# SHIELD_PICO_SMD.net
KiCad netlist of a schematic drawn in EAGLE
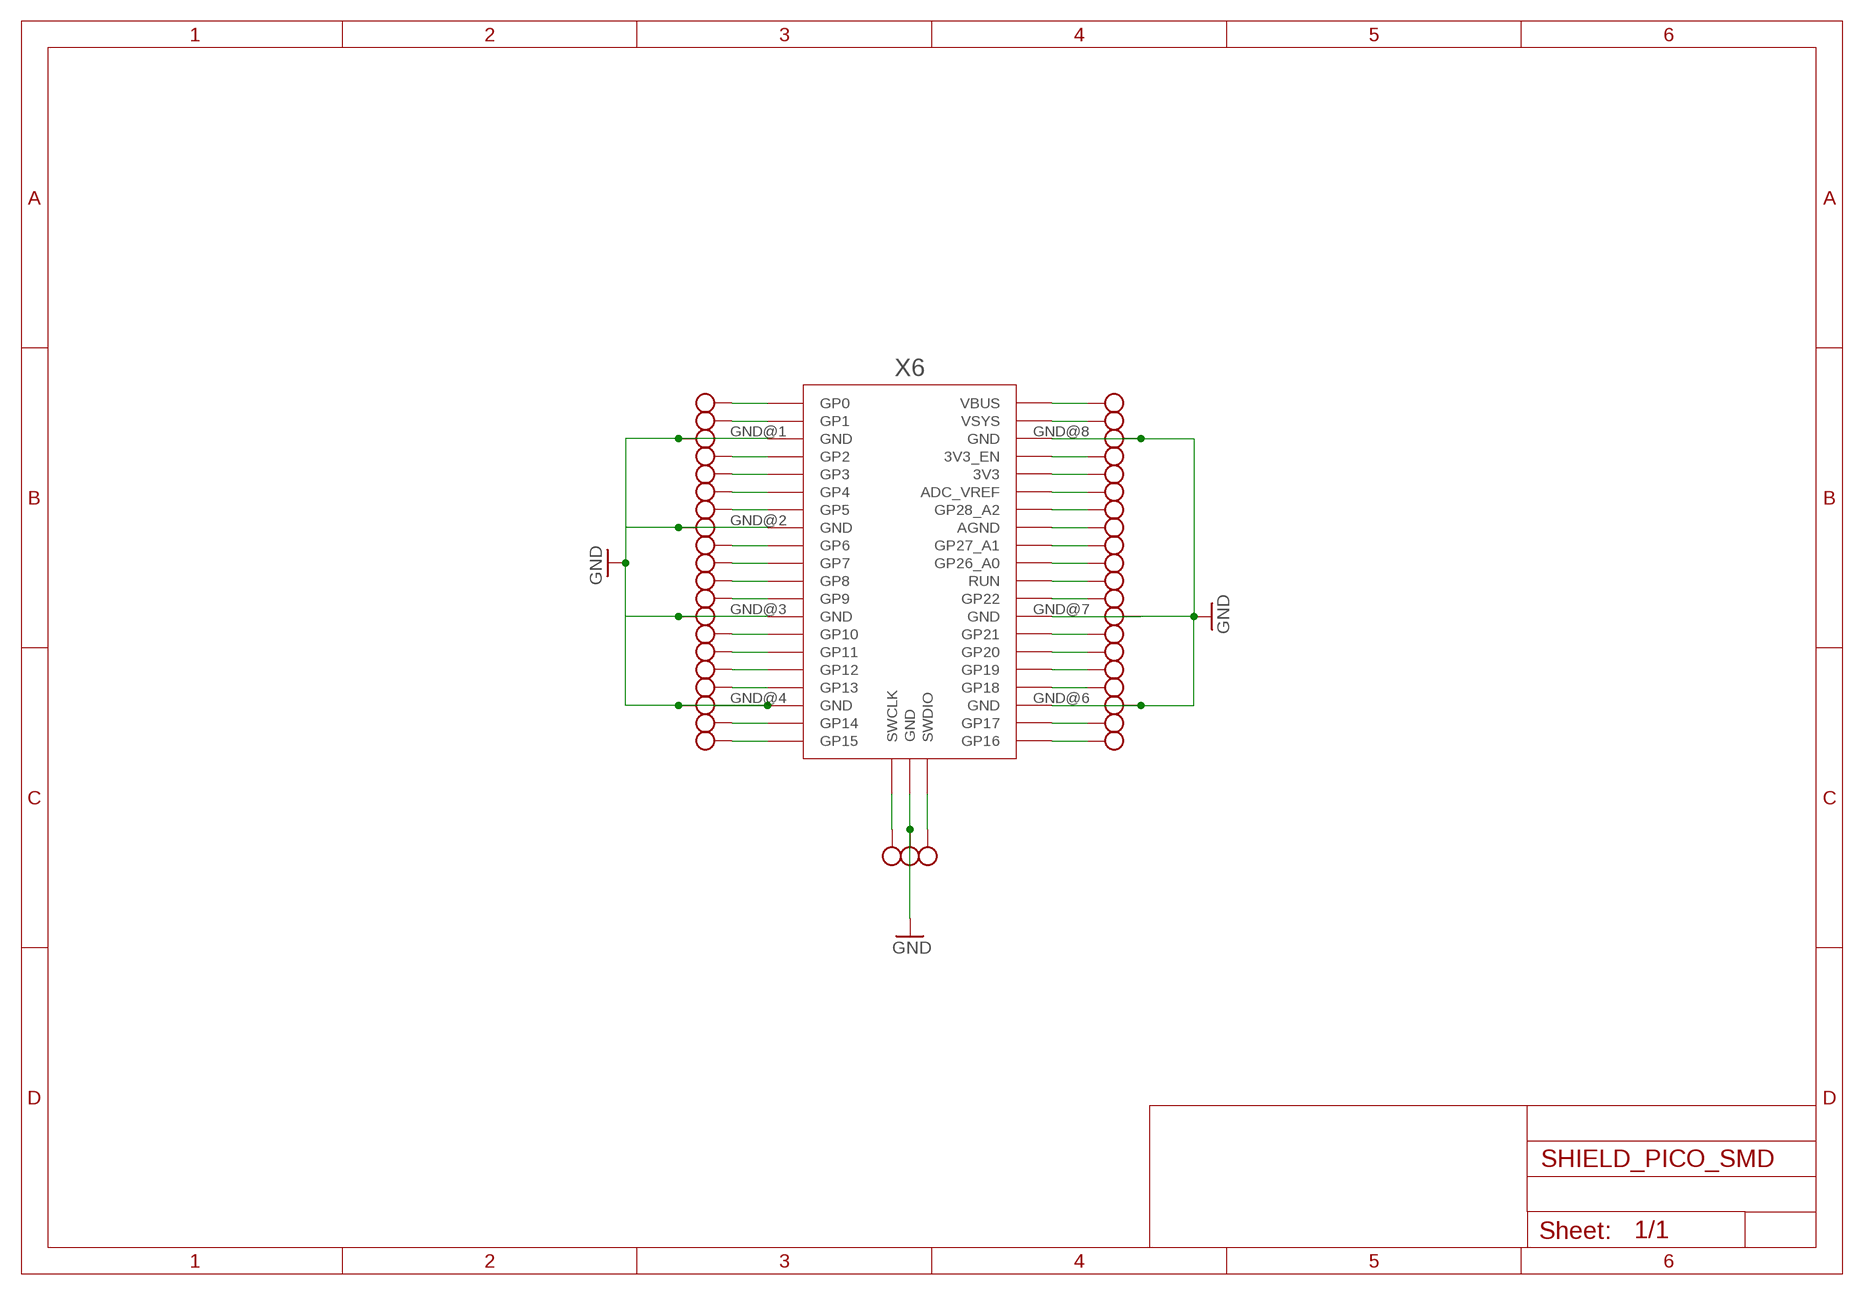
[diagram p0: schematic, sheet 1]

(export (version "E")
  (design (tool "Eeschema 10.0.6"))
  (components
    (comp (ref "X1")
      (value "AK300/12")
      (footprint "eagle-import:AK300_12")
      (libsource (lib "eagle-import") (part "AK300/12"))
    )
    (comp (ref "X2")
      (value "AK300/8")
      (footprint "eagle-import:AK300_8")
      (libsource (lib "eagle-import") (part "AK300/8"))
    )
    (comp (ref "X3")
      (value "AK300/12")
      (footprint "eagle-import:AK300_12")
      (libsource (lib "eagle-import") (part "AK300/12"))
    )
    (comp (ref "X4")
      (value "AK300/8")
      (footprint "eagle-import:AK300_8")
      (libsource (lib "eagle-import") (part "AK300/8"))
    )
    (comp (ref "X5")
      (value "AK300/3")
      (footprint "eagle-import:AK300_3")
      (libsource (lib "eagle-import") (part "AK300/3"))
    )
    (comp (ref "X6")
      (value "RPI_PICO_IG-SMD")
      (footprint "eagle-import:RPI_PICO")
      (libsource (lib "eagle-import") (part "RPI_PICO_IG-SMD"))
    )
  )
  (nets
    (net (code "1") (name "GND") (class "Default")
      (node (ref "X1") (pin "10") (pinfunction "KL_10") (pintype "passive"))
      (node (ref "X1") (pin "5") (pinfunction "KL_5") (pintype "passive"))
      (node (ref "X2") (pin "3") (pinfunction "KL_3") (pintype "passive"))
      (node (ref "X2") (pin "8") (pinfunction "KL_8") (pintype "passive"))
      (node (ref "X3") (pin "3") (pinfunction "KL_3") (pintype "passive"))
      (node (ref "X4") (pin "1") (pinfunction "KL_1") (pintype "passive"))
      (node (ref "X4") (pin "6") (pinfunction "KL_6") (pintype "passive"))
      (node (ref "X5") (pin "2") (pinfunction "KL_2") (pintype "passive"))
      (node (ref "X6") (pin "GND@1") (pinfunction "GND_GND@1") (pintype "bidirectional"))
      (node (ref "X6") (pin "GND@2") (pinfunction "GND_GND@2") (pintype "bidirectional"))
      (node (ref "X6") (pin "GND@3") (pinfunction "GND_GND@3") (pintype "bidirectional"))
      (node (ref "X6") (pin "GND@4") (pinfunction "GND_GND@4") (pintype "bidirectional"))
      (node (ref "X6") (pin "GND@5") (pinfunction "GND_GND@5") (pintype "bidirectional"))
      (node (ref "X6") (pin "GND@6") (pinfunction "GND_GND@6") (pintype "bidirectional"))
      (node (ref "X6") (pin "GND@7") (pinfunction "GND_GND@7") (pintype "bidirectional"))
      (node (ref "X6") (pin "GND@8") (pinfunction "GND_GND@8") (pintype "bidirectional"))
    )
    (net (code "2") (name "Net-(X1A-KL)") (class "Default")
      (node (ref "X1") (pin "1") (pinfunction "KL_1") (pintype "passive"))
      (node (ref "X6") (pin "GP9") (pinfunction "GP9_GP9") (pintype "bidirectional"))
    )
    (net (code "3") (name "Net-(X1C-KL)") (class "Default")
      (node (ref "X1") (pin "11") (pinfunction "KL_11") (pintype "passive"))
      (node (ref "X6") (pin "GP1") (pinfunction "GP1_GP1") (pintype "bidirectional"))
    )
    (net (code "4") (name "Net-(X1D-KL)") (class "Default")
      (node (ref "X1") (pin "12") (pinfunction "KL_12") (pintype "passive"))
      (node (ref "X6") (pin "GP0") (pinfunction "GP0_GP0") (pintype "bidirectional"))
    )
    (net (code "5") (name "Net-(X1E-KL)") (class "Default")
      (node (ref "X1") (pin "2") (pinfunction "KL_2") (pintype "passive"))
      (node (ref "X6") (pin "GP8") (pinfunction "GP8_GP8") (pintype "bidirectional"))
    )
    (net (code "6") (name "Net-(X1F-KL)") (class "Default")
      (node (ref "X1") (pin "3") (pinfunction "KL_3") (pintype "passive"))
      (node (ref "X6") (pin "GP7") (pinfunction "GP7_GP7") (pintype "bidirectional"))
    )
    (net (code "7") (name "Net-(X1G-KL)") (class "Default")
      (node (ref "X1") (pin "4") (pinfunction "KL_4") (pintype "passive"))
      (node (ref "X6") (pin "GP6") (pinfunction "GP6_GP6") (pintype "bidirectional"))
    )
    (net (code "8") (name "Net-(X1I-KL)") (class "Default")
      (node (ref "X1") (pin "6") (pinfunction "KL_6") (pintype "passive"))
      (node (ref "X6") (pin "GP5") (pinfunction "GP5_GP5") (pintype "bidirectional"))
    )
    (net (code "9") (name "Net-(X1J-KL)") (class "Default")
      (node (ref "X1") (pin "7") (pinfunction "KL_7") (pintype "passive"))
      (node (ref "X6") (pin "GP4") (pinfunction "GP4_GP4") (pintype "bidirectional"))
    )
    (net (code "10") (name "Net-(X1K-KL)") (class "Default")
      (node (ref "X1") (pin "8") (pinfunction "KL_8") (pintype "passive"))
      (node (ref "X6") (pin "GP3") (pinfunction "GP3_GP3") (pintype "bidirectional"))
    )
    (net (code "11") (name "Net-(X1L-KL)") (class "Default")
      (node (ref "X1") (pin "9") (pinfunction "KL_9") (pintype "passive"))
      (node (ref "X6") (pin "GP2") (pinfunction "GP2_GP2") (pintype "bidirectional"))
    )
    (net (code "12") (name "Net-(X2A-KL)") (class "Default")
      (node (ref "X2") (pin "1") (pinfunction "KL_1") (pintype "passive"))
      (node (ref "X6") (pin "GP15") (pinfunction "GP15_GP15") (pintype "bidirectional"))
    )
    (net (code "13") (name "Net-(X2B-KL)") (class "Default")
      (node (ref "X2") (pin "2") (pinfunction "KL_2") (pintype "passive"))
      (node (ref "X6") (pin "GP14") (pinfunction "GP14_GP14") (pintype "bidirectional"))
    )
    (net (code "14") (name "Net-(X2D-KL)") (class "Default")
      (node (ref "X2") (pin "4") (pinfunction "KL_4") (pintype "passive"))
      (node (ref "X6") (pin "GP13") (pinfunction "GP13_GP13") (pintype "bidirectional"))
    )
    (net (code "15") (name "Net-(X2E-KL)") (class "Default")
      (node (ref "X2") (pin "5") (pinfunction "KL_5") (pintype "passive"))
      (node (ref "X6") (pin "GP12") (pinfunction "GP12_GP12") (pintype "bidirectional"))
    )
    (net (code "16") (name "Net-(X2F-KL)") (class "Default")
      (node (ref "X2") (pin "6") (pinfunction "KL_6") (pintype "passive"))
      (node (ref "X6") (pin "GP11") (pinfunction "GP11_GP11") (pintype "bidirectional"))
    )
    (net (code "17") (name "Net-(X2G-KL)") (class "Default")
      (node (ref "X2") (pin "7") (pinfunction "KL_7") (pintype "passive"))
      (node (ref "X6") (pin "GP10") (pinfunction "GP10_GP10") (pintype "bidirectional"))
    )
    (net (code "18") (name "Net-(X3A-KL)") (class "Default")
      (node (ref "X3") (pin "1") (pinfunction "KL_1") (pintype "passive"))
      (node (ref "X6") (pin "VBUS") (pinfunction "VBUS_VBUS") (pintype "bidirectional"))
    )
    (net (code "19") (name "Net-(X3B-KL)") (class "Default")
      (node (ref "X3") (pin "10") (pinfunction "KL_10") (pintype "passive"))
      (node (ref "X6") (pin "GP26_A0") (pinfunction "GP26_A0_GP26_A0") (pintype "bidirectional"))
    )
    (net (code "20") (name "Net-(X3C-KL)") (class "Default")
      (node (ref "X3") (pin "11") (pinfunction "KL_11") (pintype "passive"))
      (node (ref "X6") (pin "RUN") (pinfunction "RUN_RUN") (pintype "bidirectional"))
    )
    (net (code "21") (name "Net-(X3D-KL)") (class "Default")
      (node (ref "X3") (pin "12") (pinfunction "KL_12") (pintype "passive"))
      (node (ref "X6") (pin "GP22") (pinfunction "GP22_GP22") (pintype "bidirectional"))
    )
    (net (code "22") (name "Net-(X3E-KL)") (class "Default")
      (node (ref "X3") (pin "2") (pinfunction "KL_2") (pintype "passive"))
      (node (ref "X6") (pin "VSYS") (pinfunction "VSYS_VSYS") (pintype "bidirectional"))
    )
    (net (code "23") (name "Net-(X3G-KL)") (class "Default")
      (node (ref "X3") (pin "4") (pinfunction "KL_4") (pintype "passive"))
      (node (ref "X6") (pin "3V3_EN") (pinfunction "3V3_EN_3V3_EN") (pintype "bidirectional"))
    )
    (net (code "24") (name "Net-(X3H-KL)") (class "Default")
      (node (ref "X3") (pin "5") (pinfunction "KL_5") (pintype "passive"))
      (node (ref "X6") (pin "3V3") (pinfunction "3V3_3V3") (pintype "bidirectional"))
    )
    (net (code "25") (name "Net-(X3I-KL)") (class "Default")
      (node (ref "X3") (pin "6") (pinfunction "KL_6") (pintype "passive"))
      (node (ref "X6") (pin "ADC_VREF") (pinfunction "ADC_VREF_ADC_VREF") (pintype "bidirectional"))
    )
    (net (code "26") (name "Net-(X3J-KL)") (class "Default")
      (node (ref "X3") (pin "7") (pinfunction "KL_7") (pintype "passive"))
      (node (ref "X6") (pin "GP28_A2") (pinfunction "GP28_A2_GP28_A2") (pintype "bidirectional"))
    )
    (net (code "27") (name "Net-(X3K-KL)") (class "Default")
      (node (ref "X3") (pin "8") (pinfunction "KL_8") (pintype "passive"))
      (node (ref "X6") (pin "AGND") (pinfunction "AGND_AGND") (pintype "bidirectional"))
    )
    (net (code "28") (name "Net-(X3L-KL)") (class "Default")
      (node (ref "X3") (pin "9") (pinfunction "KL_9") (pintype "passive"))
      (node (ref "X6") (pin "GP27_A1") (pinfunction "GP27_A1_GP27_A1") (pintype "bidirectional"))
    )
    (net (code "29") (name "Net-(X4B-KL)") (class "Default")
      (node (ref "X4") (pin "2") (pinfunction "KL_2") (pintype "passive"))
      (node (ref "X6") (pin "GP21") (pinfunction "GP21_GP21") (pintype "bidirectional"))
    )
    (net (code "30") (name "Net-(X4C-KL)") (class "Default")
      (node (ref "X4") (pin "3") (pinfunction "KL_3") (pintype "passive"))
      (node (ref "X6") (pin "GP20") (pinfunction "GP20_GP20") (pintype "bidirectional"))
    )
    (net (code "31") (name "Net-(X4D-KL)") (class "Default")
      (node (ref "X4") (pin "4") (pinfunction "KL_4") (pintype "passive"))
      (node (ref "X6") (pin "GP19") (pinfunction "GP19_GP19") (pintype "bidirectional"))
    )
    (net (code "32") (name "Net-(X4E-KL)") (class "Default")
      (node (ref "X4") (pin "5") (pinfunction "KL_5") (pintype "passive"))
      (node (ref "X6") (pin "GP18") (pinfunction "GP18_GP18") (pintype "bidirectional"))
    )
    (net (code "33") (name "Net-(X4G-KL)") (class "Default")
      (node (ref "X4") (pin "7") (pinfunction "KL_7") (pintype "passive"))
      (node (ref "X6") (pin "GP17") (pinfunction "GP17_GP17") (pintype "bidirectional"))
    )
    (net (code "34") (name "Net-(X4H-KL)") (class "Default")
      (node (ref "X4") (pin "8") (pinfunction "KL_8") (pintype "passive"))
      (node (ref "X6") (pin "GP16") (pinfunction "GP16_GP16") (pintype "bidirectional"))
    )
    (net (code "35") (name "Net-(X5A-KL)") (class "Default")
      (node (ref "X5") (pin "1") (pinfunction "KL_1") (pintype "passive"))
      (node (ref "X6") (pin "SWDIO") (pinfunction "SWDIO_SWDIO") (pintype "bidirectional"))
    )
    (net (code "36") (name "Net-(X5C-KL)") (class "Default")
      (node (ref "X5") (pin "3") (pinfunction "KL_3") (pintype "passive"))
      (node (ref "X6") (pin "SWCLK") (pinfunction "SWCLK_SWCLK") (pintype "bidirectional"))
    )
  )
)
